# GNSS.net
KiCad netlist of a schematic drawn in Altium Designer
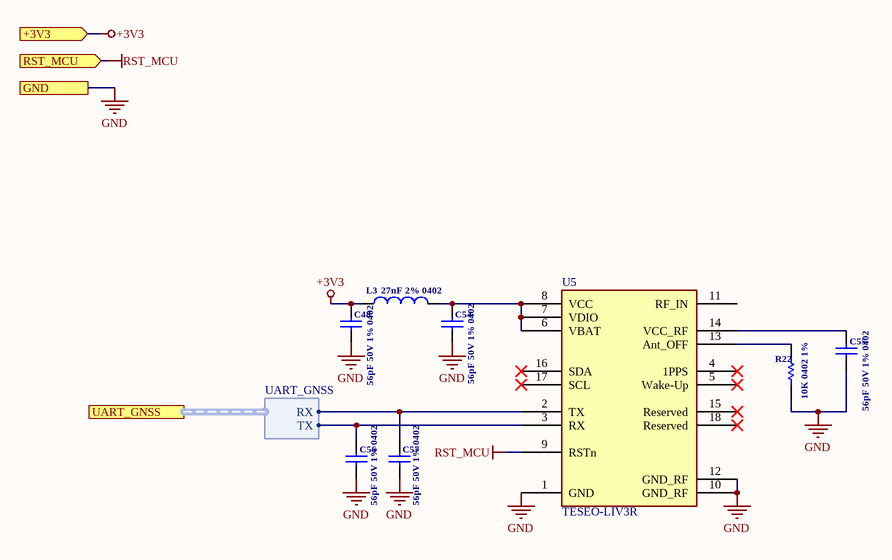
[diagram p0: GNSS.SchDoc]

(export (version "E")
  (design (tool "Eeschema 10.0.6"))
  (components
    (comp (ref "C48")
      (value "56pF 50V 1% 0402")
      (description "56 pF ±1% 50V Ceramic Capacitor C0G, NP0 0402 (1005 Metric)")
      (libsource (lib "CondensadoresGenericos") (part "CC0402FRNPO9BN560"))
    )
    (comp (ref "C54")
      (value "56pF 50V 1% 0402")
      (description "56 pF ±1% 50V Ceramic Capacitor C0G, NP0 0402 (1005 Metric)")
      (libsource (lib "CondensadoresGenericos") (part "CC0402FRNPO9BN560"))
    )
    (comp (ref "C55")
      (value "56pF 50V 1% 0402")
      (description "56 pF ±1% 50V Ceramic Capacitor C0G, NP0 0402 (1005 Metric)")
      (libsource (lib "CondensadoresGenericos") (part "CC0402FRNPO9BN560"))
    )
    (comp (ref "C56")
      (value "56pF 50V 1% 0402")
      (description "56 pF ±1% 50V Ceramic Capacitor C0G, NP0 0402 (1005 Metric)")
      (libsource (lib "CondensadoresGenericos") (part "CC0402FRNPO9BN560"))
    )
    (comp (ref "C57")
      (value "56pF 50V 1% 0402")
      (description "56 pF ±1% 50V Ceramic Capacitor C0G, NP0 0402 (1005 Metric)")
      (libsource (lib "CondensadoresGenericos") (part "CC0402FRNPO9BN560"))
    )
    (comp (ref "L3")
      (value "27nF 2% 0402")
      (description "27 nH Unshielded Multilayer Inductor 350 mA 460mOhm Max 0402 (1005 Metric) -")
      (libsource (lib "BobinasGenericas") (part "LQG15HS27NG02D"))
    )
    (comp (ref "R22")
      (value "10K 0402 1%")
      (footprint "Resistor_0402")
      (description "RES SMD 10K OHM 1% 1/16W 0402")
      (fields
        (field (name "MANUFACTURER") "Yageo")
        (field (name "MANUFACTURER PART NUMBER") "AC0402FR-0710KL")
      )
      (libsource (lib "ResistenciasGenericas") (part "AC0402FR-0710KL 10K 0402 1%"))
    )
    (comp (ref "U5")
      (value "TESEO-LIV3R")
      (description "series RF Receiver BeiDou, GLONASS, GNSS, GPS 1.561GHz, 1.575MHz -163dBm - - 18-LCC (9.7x10.1)")
      (libsource (lib "ST_GNSS_Receivers") (part "TESEO-LIV3R"))
    )
  )
  (nets
    (net (code "2") (name "+3V3") (class "Default")
      (node (ref "C48") (pin "2") (pinfunction "2_2") (pintype "passive"))
      (node (ref "L3") (pin "1") (pinfunction "1_1") (pintype "passive"))
    )
    (net (code "4") (name "GND") (class "Default")
      (node (ref "C55") (pin "1") (pinfunction "1_1") (pintype "passive"))
      (node (ref "C56") (pin "1") (pinfunction "1_1") (pintype "passive"))
      (node (ref "C57") (pin "1") (pinfunction "1_1") (pintype "passive"))
      (node (ref "R22") (pin "1") (pinfunction "1_1") (pintype "passive"))
      (node (ref "U5") (pin "1") (pinfunction "GND_1") (pintype "passive"))
      (node (ref "U5") (pin "10") (pinfunction "GND_RF_10") (pintype "passive"))
      (node (ref "U5") (pin "12") (pinfunction "GND_RF_12") (pintype "passive"))
    )
    (net (code "5") (name "Net-(U5-Ant_OFF)") (class "Default")
      (node (ref "R22") (pin "2") (pinfunction "2_2") (pintype "passive"))
      (node (ref "U5") (pin "13") (pinfunction "Ant_OFF_13") (pintype "passive"))
    )
    (net (code "6") (name "Net-(U5-RX)") (class "Default")
      (node (ref "C56") (pin "2") (pinfunction "2_2") (pintype "passive"))
      (node (ref "U5") (pin "3") (pinfunction "RX_3") (pintype "passive"))
    )
    (net (code "7") (name "Net-(U5-TX)") (class "Default")
      (node (ref "C57") (pin "2") (pinfunction "2_2") (pintype "passive"))
      (node (ref "U5") (pin "2") (pinfunction "TX_2") (pintype "passive"))
    )
    (net (code "8") (name "Net-(U5-VBAT)") (class "Default")
      (node (ref "C54") (pin "2") (pinfunction "2_2") (pintype "passive"))
      (node (ref "L3") (pin "2") (pinfunction "2_2") (pintype "passive"))
      (node (ref "U5") (pin "6") (pinfunction "VBAT_6") (pintype "passive"))
      (node (ref "U5") (pin "7") (pinfunction "VDIO_7") (pintype "passive"))
      (node (ref "U5") (pin "8") (pinfunction "VCC_8") (pintype "passive"))
    )
    (net (code "9") (name "Net-(U5-VCC_RF)") (class "Default")
      (node (ref "C55") (pin "2") (pinfunction "2_2") (pintype "passive"))
      (node (ref "U5") (pin "14") (pinfunction "VCC_RF_14") (pintype "passive"))
    )
    (net (code "10") (name "RST_MCU") (class "Default")
      (node (ref "U5") (pin "9") (pinfunction "RSTn_9") (pintype "passive"))
    )
    (net (code "11") (name "unconnected-(C48-Pad1)") (class "Default")
      (node (ref "C48") (pin "1") (pinfunction "1_1") (pintype "passive"))
    )
    (net (code "12") (name "unconnected-(C54-Pad1)") (class "Default")
      (node (ref "C54") (pin "1") (pinfunction "1_1") (pintype "passive"))
    )
    (net (code "13") (name "unconnected-(U5-1PPS-Pad4)") (class "Default")
      (node (ref "U5") (pin "4") (pinfunction "1PPS_4") (pintype "passive+no_connect"))
    )
    (net (code "14") (name "unconnected-(U5-RF_IN-Pad11)") (class "Default")
      (node (ref "U5") (pin "11") (pinfunction "RF_IN_11") (pintype "passive"))
    )
    (net (code "15") (name "unconnected-(U5-Reserved-Pad15)") (class "Default")
      (node (ref "U5") (pin "15") (pinfunction "Reserved_15") (pintype "passive+no_connect"))
    )
    (net (code "16") (name "unconnected-(U5-Reserved-Pad18)") (class "Default")
      (node (ref "U5") (pin "18") (pinfunction "Reserved_18") (pintype "passive+no_connect"))
    )
    (net (code "17") (name "unconnected-(U5-SCL-Pad17)") (class "Default")
      (node (ref "U5") (pin "17") (pinfunction "SCL_17") (pintype "passive+no_connect"))
    )
    (net (code "18") (name "unconnected-(U5-SDA-Pad16)") (class "Default")
      (node (ref "U5") (pin "16") (pinfunction "SDA_16") (pintype "passive+no_connect"))
    )
    (net (code "19") (name "unconnected-(U5-Wake-Up-Pad5)") (class "Default")
      (node (ref "U5") (pin "5") (pinfunction "Wake-Up_5") (pintype "passive+no_connect"))
    )
  )
)
